# Sheet1.net
KiCad netlist of a schematic drawn in Altium Designer
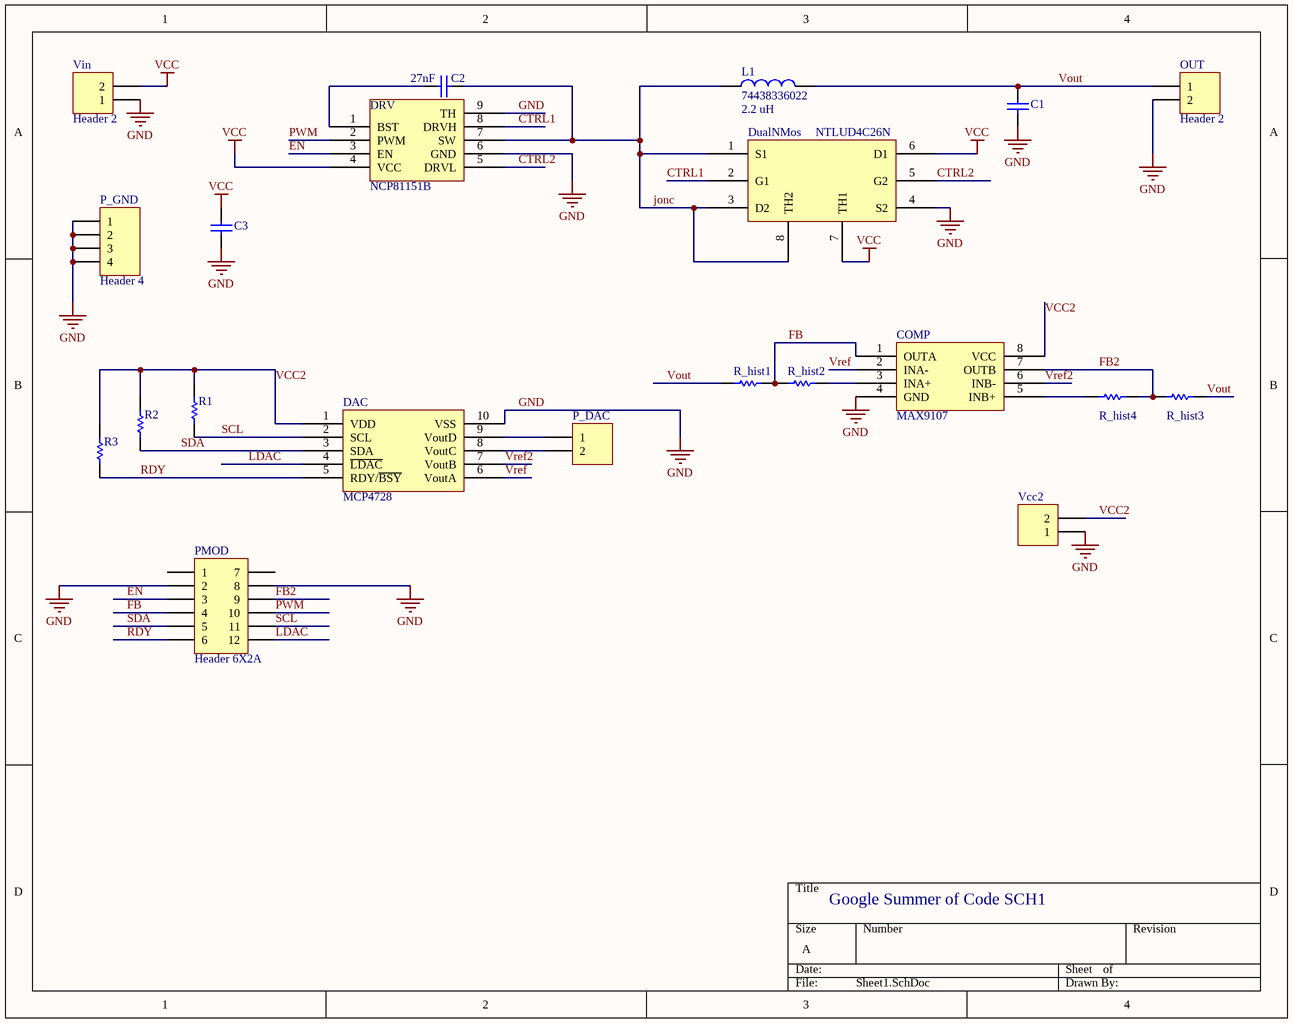
[diagram p0: Sheet1.SchDoc]

(export (version "E")
  (design (tool "Eeschema 10.0.6"))
  (components
    (comp (ref "C1")
      (value "Cap")
      (footprint "Miscellaneous Devices:C1210_M")
      (description "Capacitor")
      (fields (field (name "PUBLISHER") "Altium Limited"))
      (libsource (lib "Miscellaneous Devices") (part "Cap"))
    )
    (comp (ref "C2")
      (value "27nF")
      (footprint "C0805")
      (description "Capacitor")
      (fields (field (name "Comment") "Cap") (field (name "PUBLISHER") "Altium Limited"))
      (libsource (lib "Miscellaneous Devices") (part "Cap"))
    )
    (comp (ref "C3")
      (value "Cap")
      (footprint "Miscellaneous Devices:C1210_M")
      (description "Capacitor")
      (fields (field (name "PUBLISHER") "Altium Limited"))
      (libsource (lib "Miscellaneous Devices") (part "Cap"))
    )
    (comp (ref "COMP") (value "MAX9107") (footprint "SOT23-8") (libsource (lib "BuckLib") (part "MAX9107")))
    (comp (ref "DAC")
      (value "MCP4728")
      (footprint "TSSOP50P500X110-10N")
      (libsource (lib "BuckLib") (part "MCP4728"))
    )
    (comp (ref "DRV") (value "NCP81151B") (libsource (lib "BuckLib") (part "NCP81151B")))
    (comp (ref "DualNMos") (value "NTLUD4C26N") (libsource (lib "BuckLib") (part "NTLUD4C26N")))
    (comp (ref "L1")
      (value "74438336022")
      (footprint "WE-MAPI_3020")
      (description "WE-MAPI SMD Shielded Power Inductor, size 3020, 2.2 uH")
      (fields (field (name "ALTIUM_VALUE") "2.2 uH") (field (name "PUBLISHER") "Wurth Elektronik"))
      (libsource (lib "ALTIUM-WE-MAPI-rev16b") (part "74438336022"))
    )
    (comp (ref "OUT")
      (value "Header 2")
      (footprint "HDR1X2")
      (description "Header, 2-Pin")
      (fields (field (name "PUBLISHER") "Altium Limited"))
      (libsource (lib "Miscellaneous Connectors") (part "Header 2"))
    )
    (comp (ref "PMOD")
      (value "Header 6X2A")
      (footprint "HDR2X6_CEN")
      (description "Header, 6-Pin, Dual row")
      (fields (field (name "PUBLISHER") "Altium Limited"))
      (libsource (lib "Miscellaneous Connectors") (part "Header 6X2A"))
    )
    (comp (ref "P_DAC")
      (value "Header 2")
      (footprint "HDR1X2")
      (description "Header, 2-Pin")
      (fields (field (name "PUBLISHER") "Altium Limited"))
      (libsource (lib "Miscellaneous Connectors") (part "Header 2"))
    )
    (comp (ref "P_GND")
      (value "Header 4")
      (footprint "HDR1X4")
      (description "Header, 4-Pin")
      (fields (field (name "PUBLISHER") "Altium Limited"))
      (libsource (lib "Miscellaneous Connectors") (part "Header 4"))
    )
    (comp (ref "R1")
      (value "Res1")
      (footprint "C0805")
      (description "Resistor")
      (fields (field (name "PUBLISHER") "Altium Limited"))
      (libsource (lib "Miscellaneous Devices") (part "Res1"))
    )
    (comp (ref "R2")
      (value "Res1")
      (footprint "C0805")
      (description "Resistor")
      (fields (field (name "PUBLISHER") "Altium Limited"))
      (libsource (lib "Miscellaneous Devices") (part "Res1"))
    )
    (comp (ref "R3")
      (value "Res1")
      (footprint "C0805")
      (description "Resistor")
      (fields (field (name "PUBLISHER") "Altium Limited"))
      (libsource (lib "Miscellaneous Devices") (part "Res1"))
    )
    (comp (ref "R_hist1")
      (value "Res1")
      (footprint "C0805")
      (description "Resistor")
      (fields (field (name "PUBLISHER") "Altium Limited"))
      (libsource (lib "Miscellaneous Devices") (part "Res1"))
    )
    (comp (ref "R_hist2")
      (value "Res1")
      (footprint "C0805")
      (description "Resistor")
      (fields (field (name "PUBLISHER") "Altium Limited"))
      (libsource (lib "Miscellaneous Devices") (part "Res1"))
    )
    (comp (ref "R_hist3")
      (value "Res1")
      (footprint "C0805")
      (description "Resistor")
      (fields (field (name "PUBLISHER") "Altium Limited"))
      (libsource (lib "Miscellaneous Devices") (part "Res1"))
    )
    (comp (ref "R_hist4")
      (value "Res1")
      (footprint "C0805")
      (description "Resistor")
      (fields (field (name "PUBLISHER") "Altium Limited"))
      (libsource (lib "Miscellaneous Devices") (part "Res1"))
    )
    (comp (ref "Vcc2")
      (value "Header 2")
      (footprint "HDR1X2")
      (description "Header, 2-Pin")
      (fields (field (name "PUBLISHER") "Altium Limited"))
      (libsource (lib "") (part "Header 2_1"))
    )
    (comp (ref "Vin")
      (value "Header 2")
      (footprint "HDR1X2")
      (description "Header, 2-Pin")
      (fields (field (name "PUBLISHER") "Altium Limited"))
      (libsource (lib "") (part "Header 2_1"))
    )
  )
  (nets
    (net (code "1") (name "/CTRL1") (class "Default")
      (node (ref "DRV") (pin "8") (pinfunction "DRVH_8") (pintype "passive"))
      (node (ref "DualNMos") (pin "2") (pinfunction "G1_2") (pintype "passive"))
    )
    (net (code "2") (name "/CTRL2") (class "Default")
      (node (ref "DRV") (pin "5") (pinfunction "DRVL_5") (pintype "passive"))
      (node (ref "DualNMos") (pin "5") (pinfunction "G2_5") (pintype "passive"))
    )
    (net (code "3") (name "/EN") (class "Default")
      (node (ref "DRV") (pin "3") (pinfunction "EN_3") (pintype "passive"))
      (node (ref "PMOD") (pin "3") (pinfunction "3_3") (pintype "passive"))
    )
    (net (code "4") (name "/FB") (class "Default")
      (node (ref "COMP") (pin "1") (pinfunction "OUTA_1") (pintype "passive"))
      (node (ref "PMOD") (pin "4") (pinfunction "4_4") (pintype "passive"))
      (node (ref "R_hist1") (pin "1") (pinfunction "1_1") (pintype "passive"))
      (node (ref "R_hist2") (pin "2") (pinfunction "2_2") (pintype "passive"))
    )
    (net (code "5") (name "/FB2") (class "Default")
      (node (ref "COMP") (pin "7") (pinfunction "OUTB_7") (pintype "passive"))
      (node (ref "PMOD") (pin "9") (pinfunction "9_9") (pintype "passive"))
      (node (ref "R_hist3") (pin "2") (pinfunction "2_2") (pintype "passive"))
      (node (ref "R_hist4") (pin "1") (pinfunction "1_1") (pintype "passive"))
    )
    (net (code "6") (name "/LDAC") (class "Default")
      (node (ref "DAC") (pin "4") (pinfunction "~{LDAC}_4") (pintype "passive"))
      (node (ref "PMOD") (pin "12") (pinfunction "12_12") (pintype "passive"))
    )
    (net (code "7") (name "/PWM") (class "Default")
      (node (ref "DRV") (pin "2") (pinfunction "PWM_2") (pintype "passive"))
      (node (ref "PMOD") (pin "10") (pinfunction "10_10") (pintype "passive"))
    )
    (net (code "8") (name "/RDY") (class "Default")
      (node (ref "DAC") (pin "5") (pinfunction "RDY/~{BSY}_5") (pintype "passive"))
      (node (ref "PMOD") (pin "6") (pinfunction "6_6") (pintype "passive"))
      (node (ref "R3") (pin "1") (pinfunction "1_1") (pintype "passive"))
    )
    (net (code "9") (name "/SCL") (class "Default")
      (node (ref "DAC") (pin "2") (pinfunction "SCL_2") (pintype "passive"))
      (node (ref "PMOD") (pin "11") (pinfunction "11_11") (pintype "passive"))
      (node (ref "R1") (pin "1") (pinfunction "1_1") (pintype "passive"))
    )
    (net (code "10") (name "/SDA") (class "Default")
      (node (ref "DAC") (pin "3") (pinfunction "SDA_3") (pintype "passive"))
      (node (ref "PMOD") (pin "5") (pinfunction "5_5") (pintype "passive"))
      (node (ref "R2") (pin "1") (pinfunction "1_1") (pintype "passive"))
    )
    (net (code "11") (name "/VCC2") (class "Default")
      (node (ref "COMP") (pin "8") (pinfunction "VCC_8") (pintype "passive"))
      (node (ref "DAC") (pin "1") (pinfunction "VDD_1") (pintype "passive"))
      (node (ref "R1") (pin "2") (pinfunction "2_2") (pintype "passive"))
      (node (ref "R2") (pin "2") (pinfunction "2_2") (pintype "passive"))
      (node (ref "R3") (pin "2") (pinfunction "2_2") (pintype "passive"))
      (node (ref "Vcc2") (pin "2") (pinfunction "2_2") (pintype "passive"))
    )
    (net (code "12") (name "/Vout") (class "Default")
      (node (ref "C1") (pin "2") (pinfunction "2_2") (pintype "passive"))
      (node (ref "L1") (pin "2") (pinfunction "2_2") (pintype "passive"))
      (node (ref "OUT") (pin "1") (pinfunction "1_1") (pintype "passive"))
      (node (ref "R_hist1") (pin "2") (pinfunction "2_2") (pintype "passive"))
      (node (ref "R_hist3") (pin "1") (pinfunction "1_1") (pintype "passive"))
    )
    (net (code "13") (name "/Vref") (class "Default")
      (node (ref "COMP") (pin "2") (pinfunction "INA-_2") (pintype "passive"))
      (node (ref "DAC") (pin "6") (pinfunction "VoutA_6") (pintype "passive"))
    )
    (net (code "14") (name "/Vref2") (class "Default")
      (node (ref "COMP") (pin "6") (pinfunction "INB-_6") (pintype "passive"))
      (node (ref "DAC") (pin "7") (pinfunction "VoutB_7") (pintype "passive"))
    )
    (net (code "15") (name "/jonc") (class "Default")
      (node (ref "C2") (pin "1") (pinfunction "1_1") (pintype "passive"))
      (node (ref "DRV") (pin "7") (pinfunction "SW_7") (pintype "passive"))
      (node (ref "DualNMos") (pin "1") (pinfunction "S1_1") (pintype "passive"))
      (node (ref "DualNMos") (pin "3") (pinfunction "D2_3") (pintype "passive"))
      (node (ref "DualNMos") (pin "8") (pinfunction "TH2_8") (pintype "passive"))
      (node (ref "L1") (pin "1") (pinfunction "1_1") (pintype "passive"))
    )
    (net (code "16") (name "GND") (class "Default")
      (node (ref "C1") (pin "1") (pinfunction "1_1") (pintype "passive"))
      (node (ref "C3") (pin "2") (pinfunction "2_2") (pintype "passive"))
      (node (ref "COMP") (pin "4") (pinfunction "GND_4") (pintype "passive"))
      (node (ref "DAC") (pin "10") (pinfunction "VSS_10") (pintype "passive"))
      (node (ref "DRV") (pin "6") (pinfunction "GND_6") (pintype "passive"))
      (node (ref "DRV") (pin "9") (pinfunction "TH_9") (pintype "passive"))
      (node (ref "DualNMos") (pin "4") (pinfunction "S2_4") (pintype "passive"))
      (node (ref "OUT") (pin "2") (pinfunction "2_2") (pintype "passive"))
      (node (ref "PMOD") (pin "2") (pinfunction "2_2") (pintype "passive"))
      (node (ref "PMOD") (pin "8") (pinfunction "8_8") (pintype "passive"))
      (node (ref "P_GND") (pin "1") (pinfunction "1_1") (pintype "passive"))
      (node (ref "P_GND") (pin "2") (pinfunction "2_2") (pintype "passive"))
      (node (ref "P_GND") (pin "3") (pinfunction "3_3") (pintype "passive"))
      (node (ref "P_GND") (pin "4") (pinfunction "4_4") (pintype "passive"))
      (node (ref "Vcc2") (pin "1") (pinfunction "1_1") (pintype "passive"))
      (node (ref "Vin") (pin "1") (pinfunction "1_1") (pintype "passive"))
    )
    (net (code "17") (name "Net-(COMP-INA+)") (class "Default")
      (node (ref "COMP") (pin "3") (pinfunction "INA+_3") (pintype "passive"))
      (node (ref "R_hist2") (pin "1") (pinfunction "1_1") (pintype "passive"))
    )
    (net (code "18") (name "Net-(COMP-INB+)") (class "Default")
      (node (ref "COMP") (pin "5") (pinfunction "INB+_5") (pintype "passive"))
      (node (ref "R_hist4") (pin "2") (pinfunction "2_2") (pintype "passive"))
    )
    (net (code "19") (name "Net-(DAC-VoutC)") (class "Default")
      (node (ref "DAC") (pin "8") (pinfunction "VoutC_8") (pintype "passive"))
      (node (ref "P_DAC") (pin "2") (pinfunction "2_2") (pintype "passive"))
    )
    (net (code "20") (name "Net-(DAC-VoutD)") (class "Default")
      (node (ref "DAC") (pin "9") (pinfunction "VoutD_9") (pintype "passive"))
      (node (ref "P_DAC") (pin "1") (pinfunction "1_1") (pintype "passive"))
    )
    (net (code "21") (name "Net-(DRV-BST)") (class "Default")
      (node (ref "C2") (pin "2") (pinfunction "2_2") (pintype "passive"))
      (node (ref "DRV") (pin "1") (pinfunction "BST_1") (pintype "passive"))
    )
    (net (code "22") (name "VCC") (class "Default")
      (node (ref "C3") (pin "1") (pinfunction "1_1") (pintype "passive"))
      (node (ref "DRV") (pin "4") (pinfunction "VCC_4") (pintype "passive"))
      (node (ref "DualNMos") (pin "6") (pinfunction "D1_6") (pintype "passive"))
      (node (ref "DualNMos") (pin "7") (pinfunction "TH1_7") (pintype "passive"))
      (node (ref "Vin") (pin "2") (pinfunction "2_2") (pintype "passive"))
    )
    (net (code "23") (name "unconnected-(PMOD-Pad1)") (class "Default")
      (node (ref "PMOD") (pin "1") (pinfunction "1_1") (pintype "passive"))
    )
    (net (code "24") (name "unconnected-(PMOD-Pad7)") (class "Default")
      (node (ref "PMOD") (pin "7") (pinfunction "7_7") (pintype "passive"))
    )
  )
)
